# meter.net
KiCad netlist of a schematic drawn in EAGLE
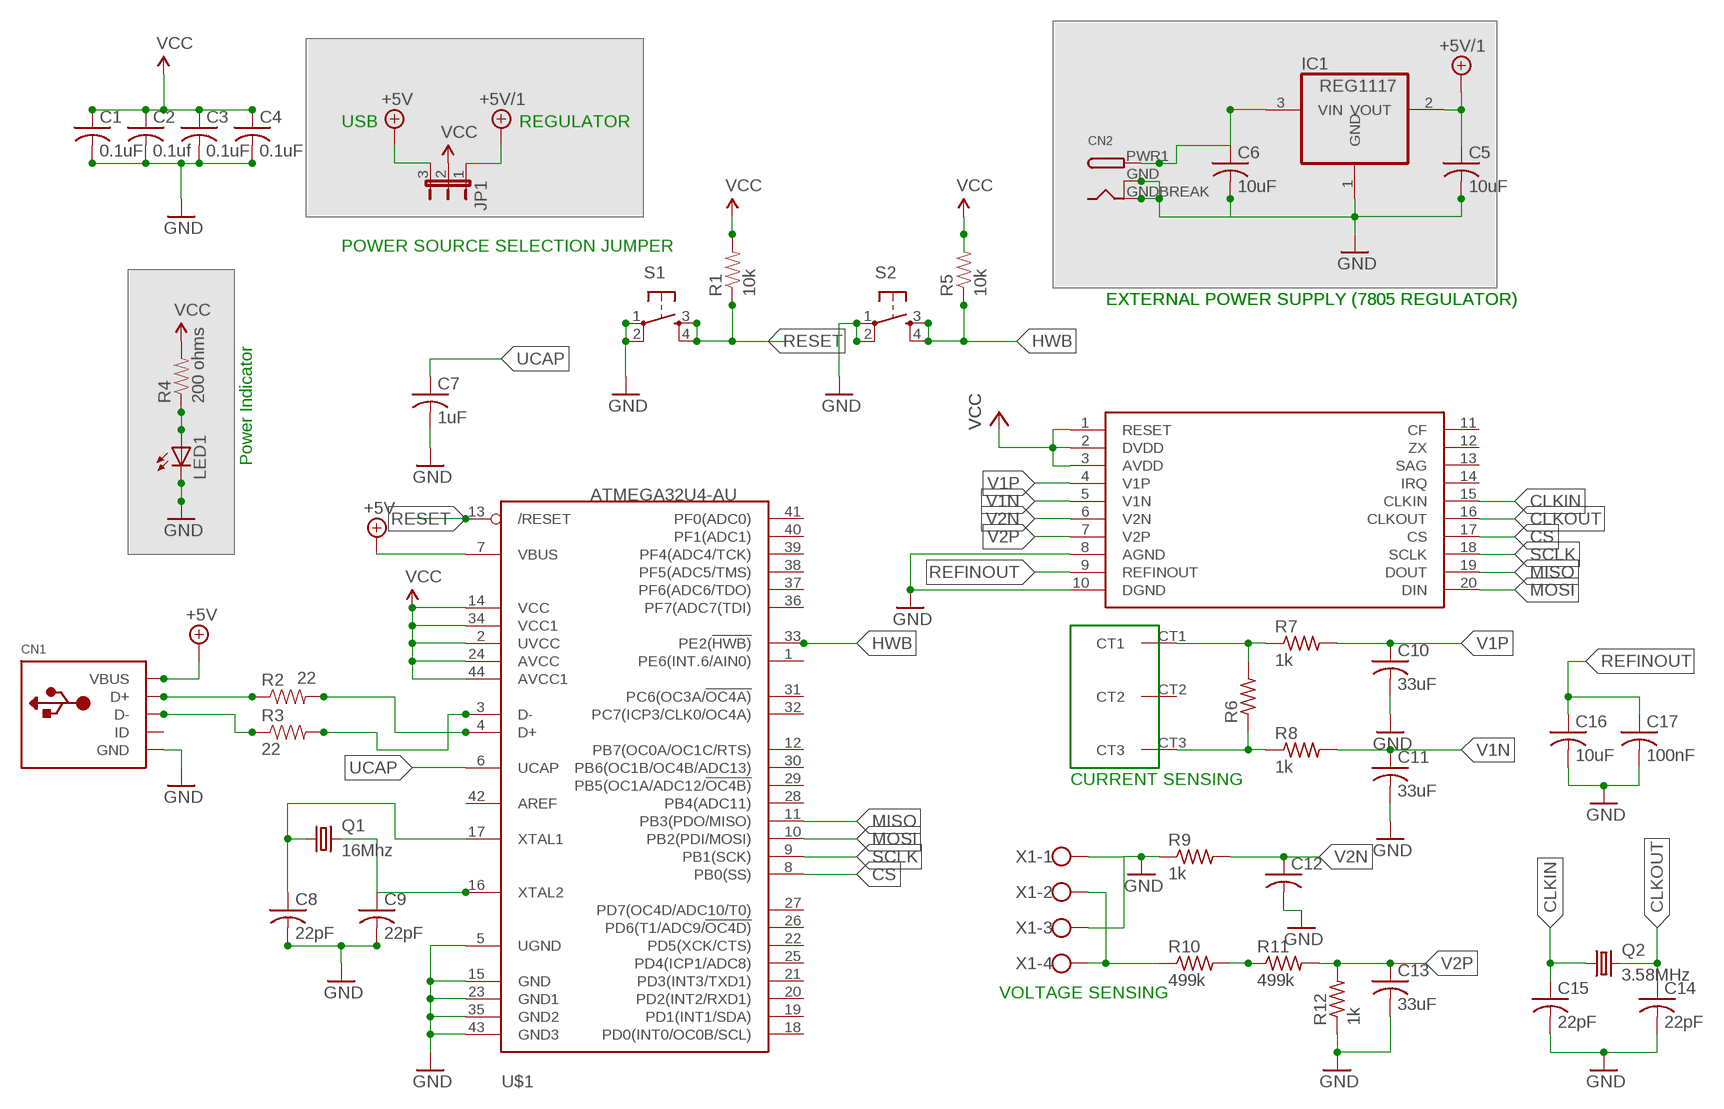
[diagram p0: schematic, sheet 1]

(export (version "E")
  (design (tool "Eeschema 10.0.6"))
  (components
    (comp (ref "C1")
      (value "0.1uF")
      (footprint "eagle-import:C0603")
      (libsource (lib "eagle-import") (part "C-USC0603"))
    )
    (comp (ref "C2")
      (value "0.1uf")
      (footprint "eagle-import:C0603")
      (libsource (lib "eagle-import") (part "C-USC0603"))
    )
    (comp (ref "C3")
      (value "0.1uF")
      (footprint "eagle-import:C0603")
      (libsource (lib "eagle-import") (part "C-USC0603"))
    )
    (comp (ref "C4")
      (value "0.1uF")
      (footprint "eagle-import:C0603")
      (libsource (lib "eagle-import") (part "C-USC0603"))
    )
    (comp (ref "C5")
      (value "10uF")
      (footprint "eagle-import:C0603")
      (libsource (lib "eagle-import") (part "C-USC0603"))
    )
    (comp (ref "C6")
      (value "10uF")
      (footprint "eagle-import:C0603")
      (libsource (lib "eagle-import") (part "C-USC0603"))
    )
    (comp (ref "C7")
      (value "1uF")
      (footprint "eagle-import:C0603")
      (libsource (lib "eagle-import") (part "C-USC0603"))
    )
    (comp (ref "C8")
      (value "22pF")
      (footprint "eagle-import:C0603")
      (libsource (lib "eagle-import") (part "C-USC0603"))
    )
    (comp (ref "C9")
      (value "22pF")
      (footprint "eagle-import:C0603")
      (libsource (lib "eagle-import") (part "C-USC0603"))
    )
    (comp (ref "C10")
      (value "33uF")
      (footprint "eagle-import:C0603")
      (libsource (lib "eagle-import") (part "C-USC0603"))
    )
    (comp (ref "C11")
      (value "33uF")
      (footprint "eagle-import:C0603")
      (libsource (lib "eagle-import") (part "C-USC0603"))
    )
    (comp (ref "C12")
      (value "C-USC0603")
      (footprint "eagle-import:C0603")
      (libsource (lib "eagle-import") (part "C-USC0603"))
    )
    (comp (ref "C13")
      (value "33uF")
      (footprint "eagle-import:C0603")
      (libsource (lib "eagle-import") (part "C-USC0603"))
    )
    (comp (ref "C14")
      (value "22pF")
      (footprint "eagle-import:C0603")
      (libsource (lib "eagle-import") (part "C-USC0603"))
    )
    (comp (ref "C15")
      (value "22pF")
      (footprint "eagle-import:C0603")
      (libsource (lib "eagle-import") (part "C-USC0603"))
    )
    (comp (ref "C16")
      (value "10uF")
      (footprint "eagle-import:C0603")
      (libsource (lib "eagle-import") (part "C-USC0603"))
    )
    (comp (ref "C17")
      (value "100nF")
      (footprint "eagle-import:C0603")
      (libsource (lib "eagle-import") (part "C-USC0603"))
    )
    (comp (ref "CN1")
      (value "USBMINIB")
      (footprint "eagle-import:USB-MINIB")
      (libsource (lib "eagle-import") (part "USBMINIB"))
    )
    (comp (ref "CN2")
      (value "DCBARRELSMT")
      (footprint "eagle-import:DCJACK_2MM_SMT")
      (libsource (lib "eagle-import") (part "DCBARRELSMT"))
    )
    (comp (ref "IC1")
      (value "REG1117")
      (footprint "eagle-import:SOT223")
      (libsource (lib "eagle-import") (part "REG1117"))
    )
    (comp (ref "JP1")
      (value "JP2E")
      (footprint "eagle-import:JP2")
      (libsource (lib "eagle-import") (part "JP2E"))
    )
    (comp (ref "LED1")
      (value "LEDCHIP-LED0805")
      (footprint "eagle-import:CHIP-LED0805")
      (libsource (lib "eagle-import") (part "LEDCHIP-LED0805"))
    )
    (comp (ref "Q1")
      (value "16Mhz")
      (footprint "eagle-import:CSM-7X-DU")
      (libsource (lib "eagle-import") (part "CSM-7X-DU"))
    )
    (comp (ref "Q2")
      (value "3.58MHz")
      (footprint "eagle-import:CSM-7X-DU")
      (libsource (lib "eagle-import") (part "CSM-7X-DU"))
    )
    (comp (ref "R1")
      (value "10k")
      (footprint "eagle-import:0603-RES")
      (libsource (lib "eagle-import") (part "RESISTOR0603-RES"))
    )
    (comp (ref "R2")
      (value "22")
      (footprint "eagle-import:0603-RES")
      (libsource (lib "eagle-import") (part "RESISTOR0603-RES"))
    )
    (comp (ref "R3")
      (value "22")
      (footprint "eagle-import:0603-RES")
      (libsource (lib "eagle-import") (part "RESISTOR0603-RES"))
    )
    (comp (ref "R4")
      (value "200 ohms")
      (footprint "eagle-import:0603-RES")
      (libsource (lib "eagle-import") (part "RESISTOR0603-RES"))
    )
    (comp (ref "R5")
      (value "10k")
      (footprint "eagle-import:0603-RES")
      (libsource (lib "eagle-import") (part "RESISTOR0603-RES"))
    )
    (comp (ref "R6")
      (value "R-US_R0603")
      (footprint "eagle-import:R0603")
      (libsource (lib "eagle-import") (part "R-US_R0603"))
    )
    (comp (ref "R7")
      (value "1k")
      (footprint "eagle-import:R0603")
      (libsource (lib "eagle-import") (part "R-US_R0603"))
    )
    (comp (ref "R8")
      (value "1k")
      (footprint "eagle-import:R0603")
      (libsource (lib "eagle-import") (part "R-US_R0603"))
    )
    (comp (ref "R9")
      (value "1k")
      (footprint "eagle-import:R0603")
      (libsource (lib "eagle-import") (part "R-US_R0603"))
    )
    (comp (ref "R10")
      (value "499k")
      (footprint "eagle-import:R0603")
      (libsource (lib "eagle-import") (part "R-US_R0603"))
    )
    (comp (ref "R11")
      (value "499k")
      (footprint "eagle-import:R0603")
      (libsource (lib "eagle-import") (part "R-US_R0603"))
    )
    (comp (ref "R12")
      (value "1k")
      (footprint "eagle-import:R0603")
      (libsource (lib "eagle-import") (part "R-US_R0603"))
    )
    (comp (ref "S1")
      (value "TAC_SWITCHSMD")
      (footprint "eagle-import:TACTILE_SWITCH_SMD")
      (libsource (lib "eagle-import") (part "TAC_SWITCHSMD"))
    )
    (comp (ref "S2")
      (value "TAC_SWITCHSMD")
      (footprint "eagle-import:TACTILE_SWITCH_SMD")
      (libsource (lib "eagle-import") (part "TAC_SWITCHSMD"))
    )
    (comp (ref "U$1")
      (value "ATMEGA32U4-AU")
      (footprint "eagle-import:TQFP44")
      (libsource (lib "eagle-import") (part "ATMEGA32U4-AU"))
    )
    (comp (ref "U$2")
      (value "ADE7753")
      (footprint "eagle-import:SSOP20")
      (libsource (lib "eagle-import") (part "ADE7753"))
    )
    (comp (ref "U$3")
      (value "CT")
      (footprint "eagle-import:CT1075")
      (libsource (lib "eagle-import") (part "CT"))
    )
    (comp (ref "X1")
      (value "W239-104")
      (footprint "eagle-import:W239-104")
      (libsource (lib "eagle-import") (part "W239-104"))
    )
  )
  (nets
    (net (code "1") (name "+5V") (class "Default")
      (node (ref "CN1") (pin "VBUS") (pinfunction "VBUS_VBUS") (pintype "power_in"))
      (node (ref "JP1") (pin "3") (pinfunction "3_3") (pintype "passive"))
      (node (ref "U$1") (pin "7") (pinfunction "VBUS_7") (pintype "bidirectional"))
    )
    (net (code "2") (name "+5V{slash}1") (class "Default")
      (node (ref "C5") (pin "1") (pinfunction "1_1") (pintype "passive"))
      (node (ref "IC1") (pin "2") (pinfunction "VOUT_2") (pintype "output"))
      (node (ref "JP1") (pin "1") (pinfunction "1_1") (pintype "passive"))
    )
    (net (code "3") (name "CLKIN") (class "Default")
      (node (ref "C15") (pin "1") (pinfunction "1_1") (pintype "passive"))
      (node (ref "Q2") (pin "1") (pinfunction "1_1") (pintype "passive"))
      (node (ref "U$2") (pin "15") (pinfunction "CLKIN_15") (pintype "bidirectional"))
    )
    (net (code "4") (name "CLKOUT") (class "Default")
      (node (ref "C14") (pin "1") (pinfunction "1_1") (pintype "passive"))
      (node (ref "Q2") (pin "2") (pinfunction "2_2") (pintype "passive"))
      (node (ref "U$2") (pin "16") (pinfunction "CLKOUT_16") (pintype "bidirectional"))
    )
    (net (code "5") (name "CS") (class "Default")
      (node (ref "U$1") (pin "8") (pinfunction "PB0(SS)_8") (pintype "bidirectional"))
      (node (ref "U$2") (pin "17") (pinfunction "CS_17") (pintype "bidirectional"))
    )
    (net (code "6") (name "GND") (class "Default")
      (node (ref "C1") (pin "2") (pinfunction "2_2") (pintype "passive"))
      (node (ref "C10") (pin "2") (pinfunction "2_2") (pintype "passive"))
      (node (ref "C11") (pin "2") (pinfunction "2_2") (pintype "passive"))
      (node (ref "C12") (pin "2") (pinfunction "2_2") (pintype "passive"))
      (node (ref "C13") (pin "2") (pinfunction "2_2") (pintype "passive"))
      (node (ref "C14") (pin "2") (pinfunction "2_2") (pintype "passive"))
      (node (ref "C15") (pin "2") (pinfunction "2_2") (pintype "passive"))
      (node (ref "C16") (pin "2") (pinfunction "2_2") (pintype "passive"))
      (node (ref "C17") (pin "2") (pinfunction "2_2") (pintype "passive"))
      (node (ref "C2") (pin "2") (pinfunction "2_2") (pintype "passive"))
      (node (ref "C3") (pin "2") (pinfunction "2_2") (pintype "passive"))
      (node (ref "C4") (pin "2") (pinfunction "2_2") (pintype "passive"))
      (node (ref "C5") (pin "2") (pinfunction "2_2") (pintype "passive"))
      (node (ref "C6") (pin "2") (pinfunction "2_2") (pintype "passive"))
      (node (ref "C7") (pin "2") (pinfunction "2_2") (pintype "passive"))
      (node (ref "C8") (pin "2") (pinfunction "2_2") (pintype "passive"))
      (node (ref "C9") (pin "2") (pinfunction "2_2") (pintype "passive"))
      (node (ref "CN1") (pin "GND") (pinfunction "GND_GND") (pintype "power_in"))
      (node (ref "CN2") (pin "GND") (pinfunction "GNDBREAK_GND") (pintype "power_in"))
      (node (ref "CN2") (pin "GNDBREAK") (pinfunction "GND_GNDBREAK") (pintype "power_in"))
      (node (ref "IC1") (pin "1") (pinfunction "GND_1") (pintype "power_in"))
      (node (ref "LED1") (pin "C") (pinfunction "C_C") (pintype "passive"))
      (node (ref "R12") (pin "1") (pinfunction "1_1") (pintype "passive"))
      (node (ref "R9") (pin "1") (pinfunction "1_1") (pintype "passive"))
      (node (ref "S1") (pin "1") (pinfunction "1_1") (pintype "passive"))
      (node (ref "S1") (pin "2") (pinfunction "2_2") (pintype "passive"))
      (node (ref "S2") (pin "1") (pinfunction "1_1") (pintype "passive"))
      (node (ref "S2") (pin "2") (pinfunction "2_2") (pintype "passive"))
      (node (ref "U$1") (pin "15") (pinfunction "GND_15") (pintype "bidirectional"))
      (node (ref "U$1") (pin "23") (pinfunction "GND1_23") (pintype "bidirectional"))
      (node (ref "U$1") (pin "35") (pinfunction "GND2_35") (pintype "bidirectional"))
      (node (ref "U$1") (pin "43") (pinfunction "GND3_43") (pintype "bidirectional"))
      (node (ref "U$1") (pin "5") (pinfunction "UGND_5") (pintype "bidirectional"))
      (node (ref "U$2") (pin "10") (pinfunction "DGND_10") (pintype "bidirectional"))
      (node (ref "U$2") (pin "8") (pinfunction "AGND_8") (pintype "bidirectional"))
      (node (ref "X1") (pin "1") (pinfunction "KL_1") (pintype "passive"))
      (node (ref "X1") (pin "3") (pinfunction "KL_3") (pintype "passive"))
    )
    (net (code "7") (name "HWB") (class "Default")
      (node (ref "R5") (pin "1") (pinfunction "1_1") (pintype "passive"))
      (node (ref "S2") (pin "3") (pinfunction "3_3") (pintype "passive"))
      (node (ref "S2") (pin "4") (pinfunction "4_4") (pintype "passive"))
      (node (ref "U$1") (pin "33") (pinfunction "PE2(~{HWB})_33") (pintype "bidirectional"))
    )
    (net (code "8") (name "MISO") (class "Default")
      (node (ref "U$1") (pin "11") (pinfunction "PB3(PDO/MISO)_11") (pintype "bidirectional"))
      (node (ref "U$2") (pin "19") (pinfunction "DOUT_19") (pintype "bidirectional"))
    )
    (net (code "9") (name "MOSI") (class "Default")
      (node (ref "U$1") (pin "10") (pinfunction "PB2(PDI/MOSI)_10") (pintype "bidirectional"))
      (node (ref "U$2") (pin "20") (pinfunction "DIN_20") (pintype "bidirectional"))
    )
    (net (code "10") (name "Net-(CN1-PadD+)") (class "Default")
      (node (ref "CN1") (pin "D+") (pinfunction "D+_D+") (pintype "bidirectional"))
      (node (ref "R2") (pin "1") (pinfunction "1_1") (pintype "passive"))
    )
    (net (code "11") (name "Net-(CN1-PadD-)") (class "Default")
      (node (ref "CN1") (pin "D-") (pinfunction "D-_D-") (pintype "bidirectional"))
      (node (ref "R3") (pin "1") (pinfunction "1_1") (pintype "passive"))
    )
    (net (code "12") (name "Net-(CN2-PWR)") (class "Default")
      (node (ref "C6") (pin "1") (pinfunction "1_1") (pintype "passive"))
      (node (ref "CN2") (pin "PWR1") (pinfunction "PWR_PWR1") (pintype "power_in"))
      (node (ref "IC1") (pin "3") (pinfunction "VIN_3") (pintype "input"))
    )
    (net (code "13") (name "Net-(LED1-PadA)") (class "Default")
      (node (ref "LED1") (pin "A") (pinfunction "A_A") (pintype "passive"))
      (node (ref "R4") (pin "1") (pinfunction "1_1") (pintype "passive"))
    )
    (net (code "14") (name "Net-(R6-Pad1)") (class "Default")
      (node (ref "R6") (pin "1") (pinfunction "1_1") (pintype "passive"))
      (node (ref "R8") (pin "1") (pinfunction "1_1") (pintype "passive"))
      (node (ref "U$3") (pin "CT3") (pinfunction "CT3_CT3") (pintype "bidirectional"))
    )
    (net (code "15") (name "Net-(R6-Pad2)") (class "Default")
      (node (ref "R6") (pin "2") (pinfunction "2_2") (pintype "passive"))
      (node (ref "R7") (pin "1") (pinfunction "1_1") (pintype "passive"))
      (node (ref "U$3") (pin "CT1") (pinfunction "CT1_CT1") (pintype "bidirectional"))
    )
    (net (code "16") (name "Net-(R10-Pad2)") (class "Default")
      (node (ref "R10") (pin "2") (pinfunction "2_2") (pintype "passive"))
      (node (ref "R11") (pin "1") (pinfunction "1_1") (pintype "passive"))
    )
    (net (code "17") (name "Net-(U$1-D+)") (class "Default")
      (node (ref "R2") (pin "2") (pinfunction "2_2") (pintype "passive"))
      (node (ref "U$1") (pin "4") (pinfunction "D+_4") (pintype "bidirectional"))
    )
    (net (code "18") (name "Net-(U$1-D-)") (class "Default")
      (node (ref "R3") (pin "2") (pinfunction "2_2") (pintype "passive"))
      (node (ref "U$1") (pin "3") (pinfunction "D-_3") (pintype "bidirectional"))
    )
    (net (code "19") (name "Net-(U$1-XTAL1)") (class "Default")
      (node (ref "C8") (pin "1") (pinfunction "1_1") (pintype "passive"))
      (node (ref "Q1") (pin "1") (pinfunction "1_1") (pintype "passive"))
      (node (ref "U$1") (pin "17") (pinfunction "XTAL1_17") (pintype "bidirectional"))
    )
    (net (code "20") (name "Net-(U$1-XTAL2)") (class "Default")
      (node (ref "C9") (pin "1") (pinfunction "1_1") (pintype "passive"))
      (node (ref "Q1") (pin "2") (pinfunction "2_2") (pintype "passive"))
      (node (ref "U$1") (pin "16") (pinfunction "XTAL2_16") (pintype "bidirectional"))
    )
    (net (code "21") (name "Net-(X1B-KL)") (class "Default")
      (node (ref "R10") (pin "1") (pinfunction "1_1") (pintype "passive"))
      (node (ref "X1") (pin "2") (pinfunction "KL_2") (pintype "passive"))
      (node (ref "X1") (pin "4") (pinfunction "KL_4") (pintype "passive"))
    )
    (net (code "22") (name "REFINOUT") (class "Default")
      (node (ref "C16") (pin "1") (pinfunction "1_1") (pintype "passive"))
      (node (ref "C17") (pin "1") (pinfunction "1_1") (pintype "passive"))
      (node (ref "U$2") (pin "9") (pinfunction "REFINOUT_9") (pintype "bidirectional"))
    )
    (net (code "23") (name "RESET") (class "Default")
      (node (ref "R1") (pin "1") (pinfunction "1_1") (pintype "passive"))
      (node (ref "S1") (pin "3") (pinfunction "3_3") (pintype "passive"))
      (node (ref "S1") (pin "4") (pinfunction "4_4") (pintype "passive"))
      (node (ref "U$1") (pin "13") (pinfunction "/RESET_13") (pintype "bidirectional"))
    )
    (net (code "24") (name "SCLK") (class "Default")
      (node (ref "U$1") (pin "9") (pinfunction "PB1(SCK)_9") (pintype "bidirectional"))
      (node (ref "U$2") (pin "18") (pinfunction "SCLK_18") (pintype "bidirectional"))
    )
    (net (code "25") (name "UCAP") (class "Default")
      (node (ref "C7") (pin "1") (pinfunction "1_1") (pintype "passive"))
      (node (ref "U$1") (pin "6") (pinfunction "UCAP_6") (pintype "bidirectional"))
    )
    (net (code "26") (name "V1N") (class "Default")
      (node (ref "C11") (pin "1") (pinfunction "1_1") (pintype "passive"))
      (node (ref "R8") (pin "2") (pinfunction "2_2") (pintype "passive"))
      (node (ref "U$2") (pin "5") (pinfunction "V1N_5") (pintype "bidirectional"))
    )
    (net (code "27") (name "V1P") (class "Default")
      (node (ref "C10") (pin "1") (pinfunction "1_1") (pintype "passive"))
      (node (ref "R7") (pin "2") (pinfunction "2_2") (pintype "passive"))
      (node (ref "U$2") (pin "4") (pinfunction "V1P_4") (pintype "bidirectional"))
    )
    (net (code "28") (name "V2N") (class "Default")
      (node (ref "C12") (pin "1") (pinfunction "1_1") (pintype "passive"))
      (node (ref "R9") (pin "2") (pinfunction "2_2") (pintype "passive"))
      (node (ref "U$2") (pin "6") (pinfunction "V2N_6") (pintype "bidirectional"))
    )
    (net (code "29") (name "V2P") (class "Default")
      (node (ref "C13") (pin "1") (pinfunction "1_1") (pintype "passive"))
      (node (ref "R11") (pin "2") (pinfunction "2_2") (pintype "passive"))
      (node (ref "R12") (pin "2") (pinfunction "2_2") (pintype "passive"))
      (node (ref "U$2") (pin "7") (pinfunction "V2P_7") (pintype "bidirectional"))
    )
    (net (code "30") (name "VCC") (class "Default")
      (node (ref "C1") (pin "1") (pinfunction "1_1") (pintype "passive"))
      (node (ref "C2") (pin "1") (pinfunction "1_1") (pintype "passive"))
      (node (ref "C3") (pin "1") (pinfunction "1_1") (pintype "passive"))
      (node (ref "C4") (pin "1") (pinfunction "1_1") (pintype "passive"))
      (node (ref "JP1") (pin "2") (pinfunction "2_2") (pintype "passive"))
      (node (ref "R1") (pin "2") (pinfunction "2_2") (pintype "passive"))
      (node (ref "R4") (pin "2") (pinfunction "2_2") (pintype "passive"))
      (node (ref "R5") (pin "2") (pinfunction "2_2") (pintype "passive"))
      (node (ref "U$1") (pin "14") (pinfunction "VCC_14") (pintype "bidirectional"))
      (node (ref "U$1") (pin "2") (pinfunction "UVCC_2") (pintype "bidirectional"))
      (node (ref "U$1") (pin "24") (pinfunction "AVCC_24") (pintype "bidirectional"))
      (node (ref "U$1") (pin "34") (pinfunction "VCC1_34") (pintype "bidirectional"))
      (node (ref "U$1") (pin "44") (pinfunction "AVCC1_44") (pintype "bidirectional"))
      (node (ref "U$2") (pin "1") (pinfunction "RESET_1") (pintype "bidirectional"))
      (node (ref "U$2") (pin "2") (pinfunction "DVDD_2") (pintype "bidirectional"))
      (node (ref "U$2") (pin "3") (pinfunction "AVDD_3") (pintype "bidirectional"))
    )
    (net (code "31") (name "unconnected-(CN1-PadID)") (class "Default")
      (node (ref "CN1") (pin "ID") (pinfunction "ID_ID") (pintype "bidirectional"))
    )
    (net (code "32") (name "unconnected-(U$1-AREF-Pad42)") (class "Default")
      (node (ref "U$1") (pin "42") (pinfunction "AREF_42") (pintype "bidirectional"))
    )
    (net (code "33") (name "unconnected-(U$1-PB4(ADC11)-Pad28)") (class "Default")
      (node (ref "U$1") (pin "28") (pinfunction "PB4(ADC11)_28") (pintype "bidirectional"))
    )
    (net (code "34") (name "unconnected-(U$1-PB5(OC1A{slash}ADC12{slash}~{OC4B})-Pad29)") (class "Default")
      (node (ref "U$1") (pin "29") (pinfunction "PB5(OC1A/ADC12/~{OC4B})_29") (pintype "bidirectional"))
    )
    (net (code "35") (name "unconnected-(U$1-PB6(OC1B{slash}OC4B{slash}ADC13)-Pad30)") (class "Default")
      (node (ref "U$1") (pin "30") (pinfunction "PB6(OC1B/OC4B/ADC13)_30") (pintype "bidirectional"))
    )
    (net (code "36") (name "unconnected-(U$1-PB7(OC0A{slash}OC1C{slash}RTS)-Pad12)") (class "Default")
      (node (ref "U$1") (pin "12") (pinfunction "PB7(OC0A/OC1C/RTS)_12") (pintype "bidirectional"))
    )
    (net (code "37") (name "unconnected-(U$1-PC6(OC3A{slash}~{OC4A})-Pad31)") (class "Default")
      (node (ref "U$1") (pin "31") (pinfunction "PC6(OC3A/~{OC4A})_31") (pintype "bidirectional"))
    )
    (net (code "38") (name "unconnected-(U$1-PC7(ICP3{slash}CLK0{slash}OC4A)-Pad32)") (class "Default")
      (node (ref "U$1") (pin "32") (pinfunction "PC7(ICP3/CLK0/OC4A)_32") (pintype "bidirectional"))
    )
    (net (code "39") (name "unconnected-(U$1-PD0(INT0{slash}OC0B{slash}SCL)-Pad18)") (class "Default")
      (node (ref "U$1") (pin "18") (pinfunction "PD0(INT0/OC0B/SCL)_18") (pintype "bidirectional"))
    )
    (net (code "40") (name "unconnected-(U$1-PD1(INT1{slash}SDA)-Pad19)") (class "Default")
      (node (ref "U$1") (pin "19") (pinfunction "PD1(INT1/SDA)_19") (pintype "bidirectional"))
    )
    (net (code "41") (name "unconnected-(U$1-PD2(INT2{slash}RXD1)-Pad20)") (class "Default")
      (node (ref "U$1") (pin "20") (pinfunction "PD2(INT2/RXD1)_20") (pintype "bidirectional"))
    )
    (net (code "42") (name "unconnected-(U$1-PD3(INT3{slash}TXD1)-Pad21)") (class "Default")
      (node (ref "U$1") (pin "21") (pinfunction "PD3(INT3/TXD1)_21") (pintype "bidirectional"))
    )
    (net (code "43") (name "unconnected-(U$1-PD4(ICP1{slash}ADC8)-Pad25)") (class "Default")
      (node (ref "U$1") (pin "25") (pinfunction "PD4(ICP1/ADC8)_25") (pintype "bidirectional"))
    )
    (net (code "44") (name "unconnected-(U$1-PD5(XCK{slash}CTS)-Pad22)") (class "Default")
      (node (ref "U$1") (pin "22") (pinfunction "PD5(XCK/CTS)_22") (pintype "bidirectional"))
    )
    (net (code "45") (name "unconnected-(U$1-PD6(T1{slash}ADC9{slash}~{OC4D})-Pad26)") (class "Default")
      (node (ref "U$1") (pin "26") (pinfunction "PD6(T1/ADC9/~{OC4D})_26") (pintype "bidirectional"))
    )
    (net (code "46") (name "unconnected-(U$1-PD7(OC4D{slash}ADC10{slash}T0)-Pad27)") (class "Default")
      (node (ref "U$1") (pin "27") (pinfunction "PD7(OC4D/ADC10/T0)_27") (pintype "bidirectional"))
    )
    (net (code "47") (name "unconnected-(U$1-PE6(INT.6{slash}AIN0)-Pad1)") (class "Default")
      (node (ref "U$1") (pin "1") (pinfunction "PE6(INT.6/AIN0)_1") (pintype "bidirectional"))
    )
    (net (code "48") (name "unconnected-(U$1-PF0(ADC0)-Pad41)") (class "Default")
      (node (ref "U$1") (pin "41") (pinfunction "PF0(ADC0)_41") (pintype "bidirectional"))
    )
    (net (code "49") (name "unconnected-(U$1-PF1(ADC1)-Pad40)") (class "Default")
      (node (ref "U$1") (pin "40") (pinfunction "PF1(ADC1)_40") (pintype "bidirectional"))
    )
    (net (code "50") (name "unconnected-(U$1-PF4(ADC4{slash}TCK)-Pad39)") (class "Default")
      (node (ref "U$1") (pin "39") (pinfunction "PF4(ADC4/TCK)_39") (pintype "bidirectional"))
    )
    (net (code "51") (name "unconnected-(U$1-PF5(ADC5{slash}TMS)-Pad38)") (class "Default")
      (node (ref "U$1") (pin "38") (pinfunction "PF5(ADC5/TMS)_38") (pintype "bidirectional"))
    )
    (net (code "52") (name "unconnected-(U$1-PF6(ADC6{slash}TDO)-Pad37)") (class "Default")
      (node (ref "U$1") (pin "37") (pinfunction "PF6(ADC6/TDO)_37") (pintype "bidirectional"))
    )
    (net (code "53") (name "unconnected-(U$1-PF7(ADC7(TDI)-Pad36)") (class "Default")
      (node (ref "U$1") (pin "36") (pinfunction "PF7(ADC7(TDI)_36") (pintype "bidirectional"))
    )
    (net (code "54") (name "unconnected-(U$2-CF-Pad11)") (class "Default")
      (node (ref "U$2") (pin "11") (pinfunction "CF_11") (pintype "bidirectional"))
    )
    (net (code "55") (name "unconnected-(U$2-IRQ-Pad14)") (class "Default")
      (node (ref "U$2") (pin "14") (pinfunction "IRQ_14") (pintype "bidirectional"))
    )
    (net (code "56") (name "unconnected-(U$2-SAG-Pad13)") (class "Default")
      (node (ref "U$2") (pin "13") (pinfunction "SAG_13") (pintype "bidirectional"))
    )
    (net (code "57") (name "unconnected-(U$2-ZX-Pad12)") (class "Default")
      (node (ref "U$2") (pin "12") (pinfunction "ZX_12") (pintype "bidirectional"))
    )
    (net (code "58") (name "unconnected-(U$3-PadCT2)") (class "Default")
      (node (ref "U$3") (pin "CT2") (pinfunction "CT2_CT2") (pintype "bidirectional"))
    )
  )
)
